# swamp-cooler.net
KiCad netlist of a schematic drawn in EAGLE
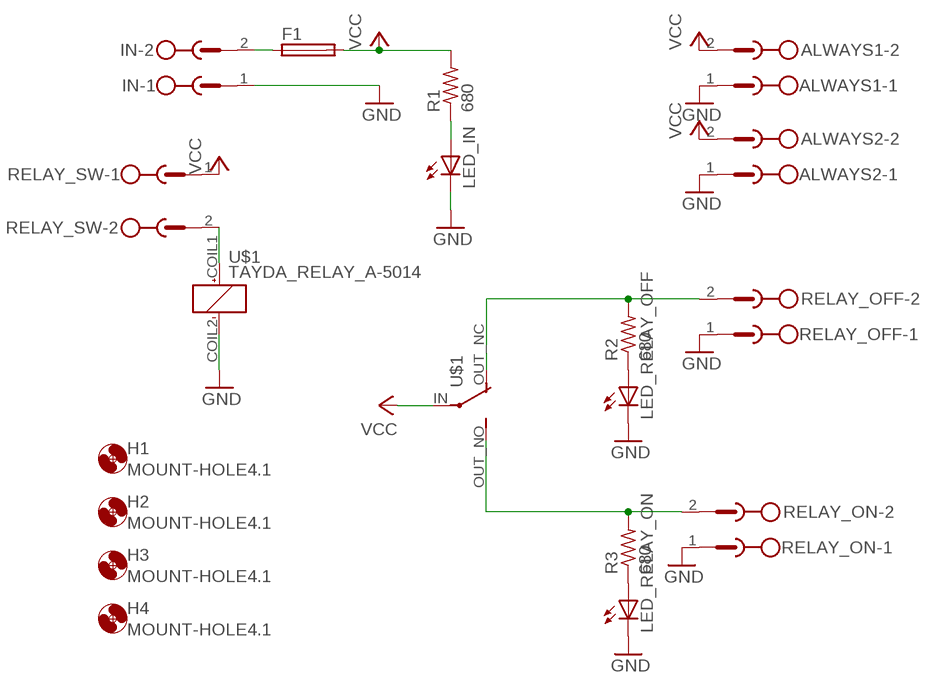
[diagram p0: schematic, sheet 1]

(export (version "E")
  (design (tool "Eeschema 10.0.6"))
  (components
    (comp (ref "ALWAYS1")
      (value "MSTBV2")
      (footprint "eagle-import:MSTBV2")
      (libsource (lib "eagle-import") (part "MSTBV2"))
    )
    (comp (ref "ALWAYS2")
      (value "MSTBV2")
      (footprint "eagle-import:MSTBV2")
      (libsource (lib "eagle-import") (part "MSTBV2"))
    )
    (comp (ref "F1")
      (value "SH22,5A")
      (footprint "eagle-import:SH22,5A")
      (fields (field (name "MPN") "0031.7701.11"))
      (libsource (lib "eagle-import") (part "SH22,5A"))
    )
    (comp (ref "H1")
      (value "MOUNT-HOLE4.1")
      (footprint "eagle-import:4,1")
      (libsource (lib "eagle-import") (part "MOUNT-HOLE4.1"))
    )
    (comp (ref "H2")
      (value "MOUNT-HOLE4.1")
      (footprint "eagle-import:4,1")
      (libsource (lib "eagle-import") (part "MOUNT-HOLE4.1"))
    )
    (comp (ref "H3")
      (value "MOUNT-HOLE4.1")
      (footprint "eagle-import:4,1")
      (libsource (lib "eagle-import") (part "MOUNT-HOLE4.1"))
    )
    (comp (ref "H4")
      (value "MOUNT-HOLE4.1")
      (footprint "eagle-import:4,1")
      (libsource (lib "eagle-import") (part "MOUNT-HOLE4.1"))
    )
    (comp (ref "IN")
      (value "MSTBV2")
      (footprint "eagle-import:MSTBV2")
      (libsource (lib "eagle-import") (part "MSTBV2"))
    )
    (comp (ref "LED_IN")
      (value "LED5MM")
      (footprint "eagle-import:LED5MM")
      (libsource (lib "eagle-import") (part "LED5MM"))
    )
    (comp (ref "LED_RELAY_OFF")
      (value "LED5MM")
      (footprint "eagle-import:LED5MM")
      (libsource (lib "eagle-import") (part "LED5MM"))
    )
    (comp (ref "LED_RELAY_ON")
      (value "LED5MM")
      (footprint "eagle-import:LED5MM")
      (libsource (lib "eagle-import") (part "LED5MM"))
    )
    (comp (ref "R1")
      (value "680")
      (footprint "eagle-import:0204_7")
      (libsource (lib "eagle-import") (part "R-US_0204/7"))
    )
    (comp (ref "R2")
      (value "680")
      (footprint "eagle-import:0204_7")
      (libsource (lib "eagle-import") (part "R-US_0204/7"))
    )
    (comp (ref "R3")
      (value "680")
      (footprint "eagle-import:0204_7")
      (libsource (lib "eagle-import") (part "R-US_0204/7"))
    )
    (comp (ref "RELAY_OFF")
      (value "MSTBV2")
      (footprint "eagle-import:MSTBV2")
      (libsource (lib "eagle-import") (part "MSTBV2"))
    )
    (comp (ref "RELAY_ON")
      (value "MSTBV2")
      (footprint "eagle-import:MSTBV2")
      (libsource (lib "eagle-import") (part "MSTBV2"))
    )
    (comp (ref "RELAY_SW")
      (value "MSTBV2")
      (footprint "eagle-import:MSTBV2")
      (libsource (lib "eagle-import") (part "MSTBV2"))
    )
    (comp (ref "U$1")
      (value "TAYDA_RELAY_A-5014")
      (footprint "eagle-import:TAYDA_RELAY_A-5014")
      (libsource (lib "eagle-import") (part "TAYDA_RELAY_A-5014"))
    )
  )
  (nets
    (net (code "1") (name "GND") (class "Default")
      (node (ref "ALWAYS1") (pin "1") (pinfunction "SK_1") (pintype "passive"))
      (node (ref "ALWAYS2") (pin "1") (pinfunction "SK_1") (pintype "passive"))
      (node (ref "IN") (pin "1") (pinfunction "SK_1") (pintype "passive"))
      (node (ref "LED_IN") (pin "K") (pinfunction "C_K") (pintype "passive"))
      (node (ref "LED_RELAY_OFF") (pin "K") (pinfunction "C_K") (pintype "passive"))
      (node (ref "LED_RELAY_ON") (pin "K") (pinfunction "C_K") (pintype "passive"))
      (node (ref "RELAY_OFF") (pin "1") (pinfunction "SK_1") (pintype "passive"))
      (node (ref "RELAY_ON") (pin "1") (pinfunction "SK_1") (pintype "passive"))
      (node (ref "U$1") (pin "COIL2") (pinfunction "-_COIL2") (pintype "passive"))
    )
    (net (code "2") (name "Net-(INB-SK)") (class "Default")
      (node (ref "F1") (pin "1") (pinfunction "1_1") (pintype "passive"))
      (node (ref "IN") (pin "2") (pinfunction "SK_2") (pintype "passive"))
    )
    (net (code "3") (name "Net-(LED_IN-PadA)") (class "Default")
      (node (ref "LED_IN") (pin "A") (pinfunction "A_A") (pintype "passive"))
      (node (ref "R1") (pin "1") (pinfunction "1_1") (pintype "passive"))
    )
    (net (code "4") (name "Net-(LED_RELAY_OFF-PadA)") (class "Default")
      (node (ref "LED_RELAY_OFF") (pin "A") (pinfunction "A_A") (pintype "passive"))
      (node (ref "R2") (pin "1") (pinfunction "1_1") (pintype "passive"))
    )
    (net (code "5") (name "Net-(LED_RELAY_ON-PadA)") (class "Default")
      (node (ref "LED_RELAY_ON") (pin "A") (pinfunction "A_A") (pintype "passive"))
      (node (ref "R3") (pin "1") (pinfunction "1_1") (pintype "passive"))
    )
    (net (code "6") (name "Net-(RELAY_OFFB-SK)") (class "Default")
      (node (ref "R2") (pin "2") (pinfunction "2_2") (pintype "passive"))
      (node (ref "RELAY_OFF") (pin "2") (pinfunction "SK_2") (pintype "passive"))
      (node (ref "U$1") (pin "OUT_NC") (pinfunction "NC_OUT_NC") (pintype "passive"))
    )
    (net (code "7") (name "Net-(RELAY_ONB-SK)") (class "Default")
      (node (ref "R3") (pin "2") (pinfunction "2_2") (pintype "passive"))
      (node (ref "RELAY_ON") (pin "2") (pinfunction "SK_2") (pintype "passive"))
      (node (ref "U$1") (pin "OUT_NO") (pinfunction "NO_OUT_NO") (pintype "passive"))
    )
    (net (code "8") (name "Net-(RELAY_SWB-SK)") (class "Default")
      (node (ref "RELAY_SW") (pin "2") (pinfunction "SK_2") (pintype "passive"))
      (node (ref "U$1") (pin "COIL1") (pinfunction "+_COIL1") (pintype "passive"))
    )
    (net (code "9") (name "VCC") (class "Default")
      (node (ref "ALWAYS1") (pin "2") (pinfunction "SK_2") (pintype "passive"))
      (node (ref "ALWAYS2") (pin "2") (pinfunction "SK_2") (pintype "passive"))
      (node (ref "F1") (pin "2") (pinfunction "2_2") (pintype "passive"))
      (node (ref "R1") (pin "2") (pinfunction "2_2") (pintype "passive"))
      (node (ref "RELAY_SW") (pin "1") (pinfunction "SK_1") (pintype "passive"))
      (node (ref "U$1") (pin "IN") (pinfunction "IN_IN") (pintype "passive"))
    )
  )
)
